# vco.net
KiCad netlist of a schematic drawn in EAGLE
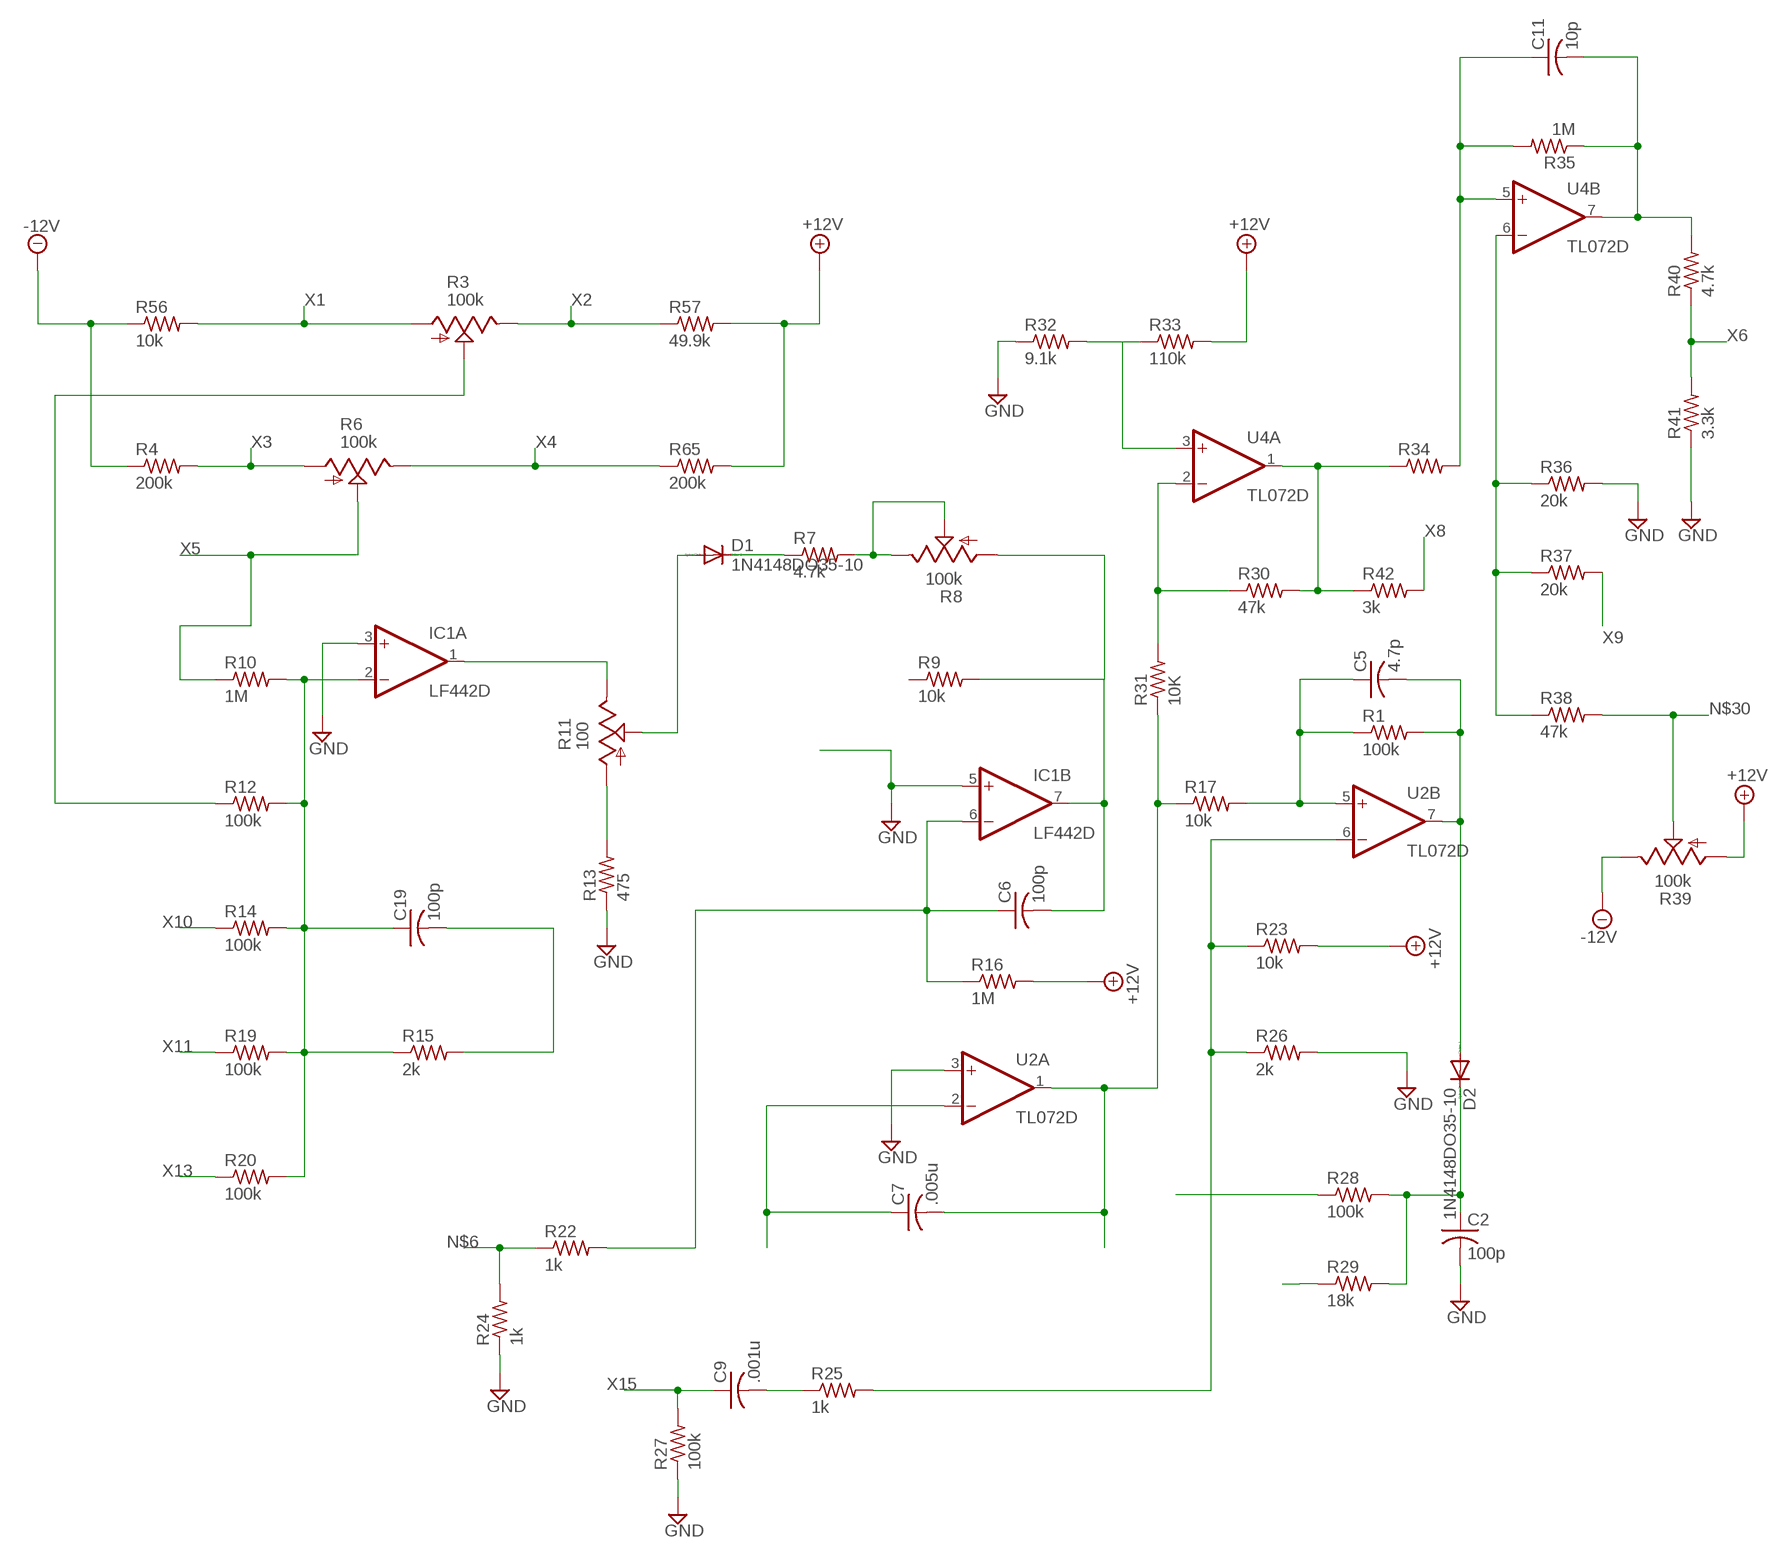
[diagram p0: schematic, sheet 1]

(export (version "E")
  (design (tool "Eeschema 10.0.6"))
  (components
    (comp (ref "C2")
      (value "100p")
      (footprint "eagle-import:C050-024X044")
      (libsource (lib "eagle-import") (part "C-US050-024X044"))
    )
    (comp (ref "C5")
      (value "4.7p")
      (footprint "eagle-import:C050-024X044")
      (libsource (lib "eagle-import") (part "C-US050-024X044"))
    )
    (comp (ref "C6")
      (value "100p")
      (footprint "eagle-import:C050-024X044")
      (libsource (lib "eagle-import") (part "C-US050-024X044"))
    )
    (comp (ref "C7")
      (value ".005u")
      (footprint "eagle-import:C050-024X044")
      (libsource (lib "eagle-import") (part "C-US050-024X044"))
    )
    (comp (ref "C9")
      (value ".001u")
      (footprint "eagle-import:C050-024X044")
      (libsource (lib "eagle-import") (part "C-US050-024X044"))
    )
    (comp (ref "C11")
      (value "10p")
      (footprint "eagle-import:C050-024X044")
      (libsource (lib "eagle-import") (part "C-US050-024X044"))
    )
    (comp (ref "C19")
      (value "100p")
      (footprint "eagle-import:C050-024X044")
      (libsource (lib "eagle-import") (part "C-US050-024X044"))
    )
    (comp (ref "D1")
      (value "1N4148DO35-10")
      (footprint "eagle-import:DO35-10")
      (libsource (lib "eagle-import") (part "1N4148DO35-10"))
    )
    (comp (ref "D2")
      (value "1N4148DO35-10")
      (footprint "eagle-import:DO35-10")
      (libsource (lib "eagle-import") (part "1N4148DO35-10"))
    )
    (comp (ref "IC1")
      (value "LF442D")
      (footprint "eagle-import:SO08")
      (libsource (lib "eagle-import") (part "LF442D"))
    )
    (comp (ref "R1")
      (value "100k")
      (footprint "eagle-import:0309_12")
      (libsource (lib "eagle-import") (part "R-US_0309/12"))
    )
    (comp (ref "R3")
      (value "100k")
      (footprint "eagle-import:PT-10")
      (libsource (lib "eagle-import") (part "TRIM_US-PT-10"))
    )
    (comp (ref "R4")
      (value "200k")
      (footprint "eagle-import:0309_12")
      (libsource (lib "eagle-import") (part "R-US_0309/12"))
    )
    (comp (ref "R6")
      (value "100k")
      (footprint "eagle-import:PT-10")
      (libsource (lib "eagle-import") (part "TRIM_US-PT-10"))
    )
    (comp (ref "R7")
      (value "4.7k")
      (footprint "eagle-import:0309_12")
      (libsource (lib "eagle-import") (part "R-US_0309/12"))
    )
    (comp (ref "R8")
      (value "100k")
      (footprint "eagle-import:PT-10")
      (libsource (lib "eagle-import") (part "TRIM_US-PT-10"))
    )
    (comp (ref "R9")
      (value "10k")
      (footprint "eagle-import:0309_12")
      (libsource (lib "eagle-import") (part "R-US_0309/12"))
    )
    (comp (ref "R10")
      (value "1M")
      (footprint "eagle-import:0309_12")
      (libsource (lib "eagle-import") (part "R-US_0309/12"))
    )
    (comp (ref "R11")
      (value "100")
      (footprint "eagle-import:PT-10")
      (libsource (lib "eagle-import") (part "TRIM_US-PT-10"))
    )
    (comp (ref "R12")
      (value "100k")
      (footprint "eagle-import:0309_12")
      (libsource (lib "eagle-import") (part "R-US_0309/12"))
    )
    (comp (ref "R13")
      (value "475")
      (footprint "eagle-import:0309_12")
      (libsource (lib "eagle-import") (part "R-US_0309/12"))
    )
    (comp (ref "R14")
      (value "100k")
      (footprint "eagle-import:0309_12")
      (libsource (lib "eagle-import") (part "R-US_0309/12"))
    )
    (comp (ref "R15")
      (value "2k")
      (footprint "eagle-import:0309_12")
      (libsource (lib "eagle-import") (part "R-US_0309/12"))
    )
    (comp (ref "R16")
      (value "1M")
      (footprint "eagle-import:0309_12")
      (libsource (lib "eagle-import") (part "R-US_0309/12"))
    )
    (comp (ref "R17")
      (value "10k")
      (footprint "eagle-import:0309_12")
      (libsource (lib "eagle-import") (part "R-US_0309/12"))
    )
    (comp (ref "R19")
      (value "100k")
      (footprint "eagle-import:0309_12")
      (libsource (lib "eagle-import") (part "R-US_0309/12"))
    )
    (comp (ref "R20")
      (value "100k")
      (footprint "eagle-import:0309_12")
      (libsource (lib "eagle-import") (part "R-US_0309/12"))
    )
    (comp (ref "R22")
      (value "1k")
      (footprint "eagle-import:0309_12")
      (libsource (lib "eagle-import") (part "R-US_0309/12"))
    )
    (comp (ref "R23")
      (value "10k")
      (footprint "eagle-import:0309_12")
      (libsource (lib "eagle-import") (part "R-US_0309/12"))
    )
    (comp (ref "R24")
      (value "1k")
      (footprint "eagle-import:0309_12")
      (libsource (lib "eagle-import") (part "R-US_0309/12"))
    )
    (comp (ref "R25")
      (value "1k")
      (footprint "eagle-import:0309_12")
      (libsource (lib "eagle-import") (part "R-US_0309/12"))
    )
    (comp (ref "R26")
      (value "2k")
      (footprint "eagle-import:0309_12")
      (libsource (lib "eagle-import") (part "R-US_0309/12"))
    )
    (comp (ref "R27")
      (value "100k")
      (footprint "eagle-import:0309_12")
      (libsource (lib "eagle-import") (part "R-US_0309/12"))
    )
    (comp (ref "R28")
      (value "100k")
      (footprint "eagle-import:0309_12")
      (libsource (lib "eagle-import") (part "R-US_0309/12"))
    )
    (comp (ref "R29")
      (value "18k")
      (footprint "eagle-import:0309_12")
      (libsource (lib "eagle-import") (part "R-US_0309/12"))
    )
    (comp (ref "R30")
      (value "47k")
      (footprint "eagle-import:0309_12")
      (libsource (lib "eagle-import") (part "R-US_0309/12"))
    )
    (comp (ref "R31")
      (value "10K")
      (footprint "eagle-import:0309_12")
      (libsource (lib "eagle-import") (part "R-US_0309/12"))
    )
    (comp (ref "R32")
      (value "9.1k")
      (footprint "eagle-import:0309_12")
      (libsource (lib "eagle-import") (part "R-US_0309/12"))
    )
    (comp (ref "R33")
      (value "110k")
      (footprint "eagle-import:0309_12")
      (libsource (lib "eagle-import") (part "R-US_0309/12"))
    )
    (comp (ref "R34")
      (value "R-US_0309/12")
      (footprint "eagle-import:0309_12")
      (libsource (lib "eagle-import") (part "R-US_0309/12"))
    )
    (comp (ref "R35")
      (value "1M")
      (footprint "eagle-import:0309_12")
      (libsource (lib "eagle-import") (part "R-US_0309/12"))
    )
    (comp (ref "R36")
      (value "20k")
      (footprint "eagle-import:0309_12")
      (libsource (lib "eagle-import") (part "R-US_0309/12"))
    )
    (comp (ref "R37")
      (value "20k")
      (footprint "eagle-import:0309_12")
      (libsource (lib "eagle-import") (part "R-US_0309/12"))
    )
    (comp (ref "R38")
      (value "47k")
      (footprint "eagle-import:0309_12")
      (libsource (lib "eagle-import") (part "R-US_0309/12"))
    )
    (comp (ref "R39")
      (value "100k")
      (footprint "eagle-import:PT-10")
      (libsource (lib "eagle-import") (part "TRIM_US-PT-10"))
    )
    (comp (ref "R40")
      (value "4.7k")
      (footprint "eagle-import:0309_12")
      (libsource (lib "eagle-import") (part "R-US_0309/12"))
    )
    (comp (ref "R41")
      (value "3.3k")
      (footprint "eagle-import:0309_12")
      (libsource (lib "eagle-import") (part "R-US_0309/12"))
    )
    (comp (ref "R42")
      (value "3k")
      (footprint "eagle-import:0309_12")
      (libsource (lib "eagle-import") (part "R-US_0309/12"))
    )
    (comp (ref "R56")
      (value "10k")
      (footprint "eagle-import:0309_12")
      (libsource (lib "eagle-import") (part "R-US_0309/12"))
    )
    (comp (ref "R57")
      (value "49.9k")
      (footprint "eagle-import:0309_12")
      (libsource (lib "eagle-import") (part "R-US_0309/12"))
    )
    (comp (ref "R65")
      (value "200k")
      (footprint "eagle-import:0309_12")
      (libsource (lib "eagle-import") (part "R-US_0309/12"))
    )
    (comp (ref "U2")
      (value "TL072D")
      (footprint "eagle-import:SO08")
      (libsource (lib "eagle-import") (part "TL072D"))
    )
    (comp (ref "U4")
      (value "TL072D")
      (footprint "eagle-import:SO08")
      (libsource (lib "eagle-import") (part "TL072D"))
    )
  )
  (nets
    (net (code "1") (name "+12V") (class "Default")
      (node (ref "R16") (pin "2") (pinfunction "2_2") (pintype "passive"))
      (node (ref "R23") (pin "2") (pinfunction "2_2") (pintype "passive"))
      (node (ref "R33") (pin "2") (pinfunction "2_2") (pintype "passive"))
      (node (ref "R39") (pin "A") (pinfunction "A_A") (pintype "passive"))
      (node (ref "R57") (pin "2") (pinfunction "2_2") (pintype "passive"))
      (node (ref "R65") (pin "2") (pinfunction "2_2") (pintype "passive"))
    )
    (net (code "2") (name "-12V") (class "Default")
      (node (ref "R39") (pin "E") (pinfunction "E_E") (pintype "passive"))
      (node (ref "R4") (pin "1") (pinfunction "1_1") (pintype "passive"))
      (node (ref "R56") (pin "1") (pinfunction "1_1") (pintype "passive"))
    )
    (net (code "3") (name "/N$6") (class "Default")
      (node (ref "R22") (pin "1") (pinfunction "1_1") (pintype "passive"))
      (node (ref "R24") (pin "2") (pinfunction "2_2") (pintype "passive"))
    )
    (net (code "4") (name "/N$30") (class "Default")
      (node (ref "R38") (pin "2") (pinfunction "2_2") (pintype "passive"))
      (node (ref "R39") (pin "S") (pinfunction "S_S") (pintype "passive"))
    )
    (net (code "5") (name "/X1") (class "Default")
      (node (ref "R3") (pin "A") (pinfunction "A_A") (pintype "passive"))
      (node (ref "R56") (pin "2") (pinfunction "2_2") (pintype "passive"))
    )
    (net (code "6") (name "/X2") (class "Default")
      (node (ref "R3") (pin "E") (pinfunction "E_E") (pintype "passive"))
      (node (ref "R57") (pin "1") (pinfunction "1_1") (pintype "passive"))
    )
    (net (code "7") (name "/X3") (class "Default")
      (node (ref "R4") (pin "2") (pinfunction "2_2") (pintype "passive"))
      (node (ref "R6") (pin "A") (pinfunction "A_A") (pintype "passive"))
    )
    (net (code "8") (name "/X4") (class "Default")
      (node (ref "R6") (pin "E") (pinfunction "E_E") (pintype "passive"))
      (node (ref "R65") (pin "1") (pinfunction "1_1") (pintype "passive"))
    )
    (net (code "9") (name "/X5") (class "Default")
      (node (ref "R10") (pin "1") (pinfunction "1_1") (pintype "passive"))
      (node (ref "R6") (pin "S") (pinfunction "S_S") (pintype "passive"))
    )
    (net (code "10") (name "/X6") (class "Default")
      (node (ref "R40") (pin "1") (pinfunction "1_1") (pintype "passive"))
      (node (ref "R41") (pin "2") (pinfunction "2_2") (pintype "passive"))
    )
    (net (code "11") (name "/X8") (class "Default")
      (node (ref "R42") (pin "2") (pinfunction "2_2") (pintype "passive"))
    )
    (net (code "12") (name "/X9") (class "Default")
      (node (ref "R37") (pin "2") (pinfunction "2_2") (pintype "passive"))
    )
    (net (code "13") (name "/X10") (class "Default")
      (node (ref "R14") (pin "1") (pinfunction "1_1") (pintype "passive"))
    )
    (net (code "14") (name "/X11") (class "Default")
      (node (ref "R19") (pin "1") (pinfunction "1_1") (pintype "passive"))
    )
    (net (code "15") (name "/X13") (class "Default")
      (node (ref "R20") (pin "1") (pinfunction "1_1") (pintype "passive"))
    )
    (net (code "16") (name "/X15") (class "Default")
      (node (ref "C9") (pin "1") (pinfunction "1_1") (pintype "passive"))
      (node (ref "R27") (pin "2") (pinfunction "2_2") (pintype "passive"))
    )
    (net (code "17") (name "GND") (class "Default")
      (node (ref "C2") (pin "2") (pinfunction "2_2") (pintype "passive"))
      (node (ref "IC1") (pin "3") (pinfunction "+IN_3") (pintype "input"))
      (node (ref "IC1") (pin "5") (pinfunction "+IN_5") (pintype "input"))
      (node (ref "R13") (pin "1") (pinfunction "1_1") (pintype "passive"))
      (node (ref "R24") (pin "1") (pinfunction "1_1") (pintype "passive"))
      (node (ref "R26") (pin "2") (pinfunction "2_2") (pintype "passive"))
      (node (ref "R27") (pin "1") (pinfunction "1_1") (pintype "passive"))
      (node (ref "R32") (pin "1") (pinfunction "1_1") (pintype "passive"))
      (node (ref "R36") (pin "2") (pinfunction "2_2") (pintype "passive"))
      (node (ref "R41") (pin "1") (pinfunction "1_1") (pintype "passive"))
      (node (ref "U2") (pin "3") (pinfunction "+IN_3") (pintype "input"))
    )
    (net (code "18") (name "Net-(C2-Pad1)") (class "Default")
      (node (ref "C2") (pin "1") (pinfunction "1_1") (pintype "passive"))
      (node (ref "D2") (pin "C") (pinfunction "C_C") (pintype "passive"))
      (node (ref "R28") (pin "2") (pinfunction "2_2") (pintype "passive"))
      (node (ref "R29") (pin "2") (pinfunction "2_2") (pintype "passive"))
    )
    (net (code "19") (name "Net-(C9-Pad2)") (class "Default")
      (node (ref "C9") (pin "2") (pinfunction "2_2") (pintype "passive"))
      (node (ref "R25") (pin "1") (pinfunction "1_1") (pintype "passive"))
    )
    (net (code "20") (name "Net-(C19-Pad2)") (class "Default")
      (node (ref "C19") (pin "2") (pinfunction "2_2") (pintype "passive"))
      (node (ref "R15") (pin "2") (pinfunction "2_2") (pintype "passive"))
    )
    (net (code "21") (name "Net-(D1-PadA)") (class "Default")
      (node (ref "D1") (pin "A") (pinfunction "A_A") (pintype "passive"))
      (node (ref "R11") (pin "S") (pinfunction "S_S") (pintype "passive"))
    )
    (net (code "22") (name "Net-(D1-PadC)") (class "Default")
      (node (ref "D1") (pin "C") (pinfunction "C_C") (pintype "passive"))
      (node (ref "R7") (pin "1") (pinfunction "1_1") (pintype "passive"))
    )
    (net (code "23") (name "Net-(IC1A--IN)") (class "Default")
      (node (ref "C19") (pin "1") (pinfunction "1_1") (pintype "passive"))
      (node (ref "IC1") (pin "2") (pinfunction "-IN_2") (pintype "input"))
      (node (ref "R10") (pin "2") (pinfunction "2_2") (pintype "passive"))
      (node (ref "R12") (pin "2") (pinfunction "2_2") (pintype "passive"))
      (node (ref "R14") (pin "2") (pinfunction "2_2") (pintype "passive"))
      (node (ref "R15") (pin "1") (pinfunction "1_1") (pintype "passive"))
      (node (ref "R19") (pin "2") (pinfunction "2_2") (pintype "passive"))
      (node (ref "R20") (pin "2") (pinfunction "2_2") (pintype "passive"))
    )
    (net (code "24") (name "Net-(IC1A-OUT)") (class "Default")
      (node (ref "IC1") (pin "1") (pinfunction "OUT_1") (pintype "output"))
      (node (ref "R11") (pin "E") (pinfunction "E_E") (pintype "passive"))
    )
    (net (code "25") (name "Net-(IC1B--IN)") (class "Default")
      (node (ref "C6") (pin "1") (pinfunction "1_1") (pintype "passive"))
      (node (ref "IC1") (pin "6") (pinfunction "-IN_6") (pintype "input"))
      (node (ref "R16") (pin "1") (pinfunction "1_1") (pintype "passive"))
      (node (ref "R22") (pin "2") (pinfunction "2_2") (pintype "passive"))
    )
    (net (code "26") (name "Net-(IC1B-OUT)") (class "Default")
      (node (ref "C6") (pin "2") (pinfunction "2_2") (pintype "passive"))
      (node (ref "IC1") (pin "7") (pinfunction "OUT_7") (pintype "output"))
      (node (ref "R8") (pin "A") (pinfunction "A_A") (pintype "passive"))
      (node (ref "R9") (pin "2") (pinfunction "2_2") (pintype "passive"))
    )
    (net (code "27") (name "Net-(R7-Pad2)") (class "Default")
      (node (ref "R7") (pin "2") (pinfunction "2_2") (pintype "passive"))
      (node (ref "R8") (pin "E") (pinfunction "E_E") (pintype "passive"))
      (node (ref "R8") (pin "S") (pinfunction "S_S") (pintype "passive"))
    )
    (net (code "28") (name "Net-(R11-PadA)") (class "Default")
      (node (ref "R11") (pin "A") (pinfunction "A_A") (pintype "passive"))
      (node (ref "R13") (pin "2") (pinfunction "2_2") (pintype "passive"))
    )
    (net (code "29") (name "Net-(R12-Pad1)") (class "Default")
      (node (ref "R12") (pin "1") (pinfunction "1_1") (pintype "passive"))
      (node (ref "R3") (pin "S") (pinfunction "S_S") (pintype "passive"))
    )
    (net (code "30") (name "Net-(U2A--IN)") (class "Default")
      (node (ref "C7") (pin "1") (pinfunction "1_1") (pintype "passive"))
      (node (ref "U2") (pin "2") (pinfunction "-IN_2") (pintype "input"))
    )
    (net (code "31") (name "Net-(U2A-OUT)") (class "Default")
      (node (ref "C7") (pin "2") (pinfunction "2_2") (pintype "passive"))
      (node (ref "R17") (pin "1") (pinfunction "1_1") (pintype "passive"))
      (node (ref "R31") (pin "1") (pinfunction "1_1") (pintype "passive"))
      (node (ref "U2") (pin "1") (pinfunction "OUT_1") (pintype "output"))
    )
    (net (code "32") (name "Net-(U2B-+IN)") (class "Default")
      (node (ref "C5") (pin "1") (pinfunction "1_1") (pintype "passive"))
      (node (ref "R1") (pin "1") (pinfunction "1_1") (pintype "passive"))
      (node (ref "R17") (pin "2") (pinfunction "2_2") (pintype "passive"))
      (node (ref "U2") (pin "5") (pinfunction "+IN_5") (pintype "input"))
    )
    (net (code "33") (name "Net-(U2B--IN)") (class "Default")
      (node (ref "R23") (pin "1") (pinfunction "1_1") (pintype "passive"))
      (node (ref "R25") (pin "2") (pinfunction "2_2") (pintype "passive"))
      (node (ref "R26") (pin "1") (pinfunction "1_1") (pintype "passive"))
      (node (ref "U2") (pin "6") (pinfunction "-IN_6") (pintype "input"))
    )
    (net (code "34") (name "Net-(U2B-OUT)") (class "Default")
      (node (ref "C5") (pin "2") (pinfunction "2_2") (pintype "passive"))
      (node (ref "D2") (pin "A") (pinfunction "A_A") (pintype "passive"))
      (node (ref "R1") (pin "2") (pinfunction "2_2") (pintype "passive"))
      (node (ref "U2") (pin "7") (pinfunction "OUT_7") (pintype "output"))
    )
    (net (code "35") (name "Net-(U4A-+IN)") (class "Default")
      (node (ref "R32") (pin "2") (pinfunction "2_2") (pintype "passive"))
      (node (ref "R33") (pin "1") (pinfunction "1_1") (pintype "passive"))
      (node (ref "U4") (pin "3") (pinfunction "+IN_3") (pintype "input"))
    )
    (net (code "36") (name "Net-(U4A--IN)") (class "Default")
      (node (ref "R30") (pin "1") (pinfunction "1_1") (pintype "passive"))
      (node (ref "R31") (pin "2") (pinfunction "2_2") (pintype "passive"))
      (node (ref "U4") (pin "2") (pinfunction "-IN_2") (pintype "input"))
    )
    (net (code "37") (name "Net-(U4A-OUT)") (class "Default")
      (node (ref "R30") (pin "2") (pinfunction "2_2") (pintype "passive"))
      (node (ref "R34") (pin "1") (pinfunction "1_1") (pintype "passive"))
      (node (ref "R42") (pin "1") (pinfunction "1_1") (pintype "passive"))
      (node (ref "U4") (pin "1") (pinfunction "OUT_1") (pintype "output"))
    )
    (net (code "38") (name "Net-(U4B-+IN)") (class "Default")
      (node (ref "C11") (pin "1") (pinfunction "1_1") (pintype "passive"))
      (node (ref "R34") (pin "2") (pinfunction "2_2") (pintype "passive"))
      (node (ref "R35") (pin "2") (pinfunction "2_2") (pintype "passive"))
      (node (ref "U4") (pin "5") (pinfunction "+IN_5") (pintype "input"))
    )
    (net (code "39") (name "Net-(U4B--IN)") (class "Default")
      (node (ref "R36") (pin "1") (pinfunction "1_1") (pintype "passive"))
      (node (ref "R37") (pin "1") (pinfunction "1_1") (pintype "passive"))
      (node (ref "R38") (pin "1") (pinfunction "1_1") (pintype "passive"))
      (node (ref "U4") (pin "6") (pinfunction "-IN_6") (pintype "input"))
    )
    (net (code "40") (name "Net-(U4B-OUT)") (class "Default")
      (node (ref "C11") (pin "2") (pinfunction "2_2") (pintype "passive"))
      (node (ref "R35") (pin "1") (pinfunction "1_1") (pintype "passive"))
      (node (ref "R40") (pin "2") (pinfunction "2_2") (pintype "passive"))
      (node (ref "U4") (pin "7") (pinfunction "OUT_7") (pintype "output"))
    )
    (net (code "41") (name "unconnected-(R9-Pad1)") (class "Default")
      (node (ref "R9") (pin "1") (pinfunction "1_1") (pintype "passive"))
    )
    (net (code "42") (name "unconnected-(R28-Pad1)") (class "Default")
      (node (ref "R28") (pin "1") (pinfunction "1_1") (pintype "passive"))
    )
    (net (code "43") (name "unconnected-(R29-Pad1)") (class "Default")
      (node (ref "R29") (pin "1") (pinfunction "1_1") (pintype "passive"))
    )
  )
)
